# project.net
KiCad netlist of a schematic drawn in EAGLE
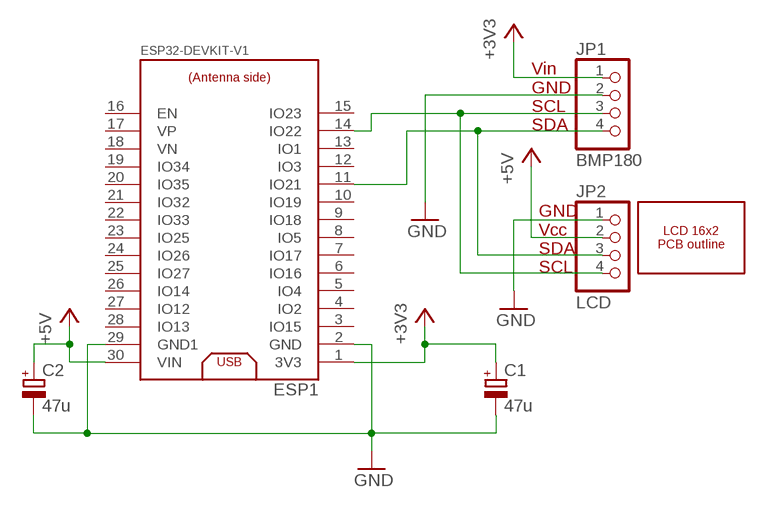
[diagram p0: schematic, sheet 1]

(export (version "E")
  (design (tool "Eeschema 10.0.6"))
  (components
    (comp (ref "C1")
      (value "47u")
      (footprint "eagle-import:E2,5-6E")
      (libsource (lib "eagle-import") (part "CPOL-EUE2,5-6E"))
    )
    (comp (ref "C2")
      (value "47u")
      (footprint "eagle-import:E2,5-6E")
      (libsource (lib "eagle-import") (part "CPOL-EUE2,5-6E"))
    )
    (comp (ref "ESP1")
      (value "ESP32DEVKITV1")
      (footprint "eagle-import:ESP32-DEVKITV1")
      (libsource (lib "eagle-import") (part "ESP32DEVKITV1"))
    )
    (comp (ref "JP1")
      (value "BMP180")
      (footprint "eagle-import:1X04")
      (libsource (lib "eagle-import") (part "PINHD-1X4"))
    )
    (comp (ref "JP2")
      (value "LCD")
      (footprint "eagle-import:1X04")
      (libsource (lib "eagle-import") (part "PINHD-1X4"))
    )
    (comp (ref "LCD1")
      (value "OUTLINES")
      (footprint "eagle-import:LCD162-OUTLINE")
      (libsource (lib "eagle-import") (part "OUTLINES"))
    )
  )
  (nets
    (net (code "1") (name "+3V3") (class "Default")
      (node (ref "C1") (pin "+") (pinfunction "+_+") (pintype "passive"))
      (node (ref "ESP1") (pin "1") (pinfunction "3V3_1") (pintype "bidirectional"))
      (node (ref "JP1") (pin "1") (pinfunction "1_1") (pintype "passive"))
    )
    (net (code "2") (name "+5V") (class "Default")
      (node (ref "C2") (pin "+") (pinfunction "+_+") (pintype "passive"))
      (node (ref "ESP1") (pin "30") (pinfunction "VIN_30") (pintype "bidirectional"))
      (node (ref "JP2") (pin "2") (pinfunction "2_2") (pintype "passive"))
    )
    (net (code "3") (name "GND") (class "Default")
      (node (ref "C1") (pin "-") (pinfunction "-_-") (pintype "passive"))
      (node (ref "C2") (pin "-") (pinfunction "-_-") (pintype "passive"))
      (node (ref "ESP1") (pin "2") (pinfunction "GND_2") (pintype "bidirectional"))
      (node (ref "ESP1") (pin "29") (pinfunction "GND1_29") (pintype "bidirectional"))
      (node (ref "JP1") (pin "2") (pinfunction "2_2") (pintype "passive"))
      (node (ref "JP2") (pin "1") (pinfunction "1_1") (pintype "passive"))
    )
    (net (code "4") (name "Net-(ESP1-IO21)") (class "Default")
      (node (ref "ESP1") (pin "11") (pinfunction "IO21_11") (pintype "bidirectional"))
      (node (ref "JP1") (pin "4") (pinfunction "4_4") (pintype "passive"))
      (node (ref "JP2") (pin "3") (pinfunction "3_3") (pintype "passive"))
    )
    (net (code "5") (name "Net-(ESP1-IO22)") (class "Default")
      (node (ref "ESP1") (pin "14") (pinfunction "IO22_14") (pintype "bidirectional"))
      (node (ref "JP1") (pin "3") (pinfunction "3_3") (pintype "passive"))
      (node (ref "JP2") (pin "4") (pinfunction "4_4") (pintype "passive"))
    )
    (net (code "6") (name "unconnected-(ESP1-EN-Pad16)") (class "Default")
      (node (ref "ESP1") (pin "16") (pinfunction "EN_16") (pintype "bidirectional"))
    )
    (net (code "7") (name "unconnected-(ESP1-IO1-Pad13)") (class "Default")
      (node (ref "ESP1") (pin "13") (pinfunction "IO1_13") (pintype "bidirectional"))
    )
    (net (code "8") (name "unconnected-(ESP1-IO2-Pad4)") (class "Default")
      (node (ref "ESP1") (pin "4") (pinfunction "IO2_4") (pintype "bidirectional"))
    )
    (net (code "9") (name "unconnected-(ESP1-IO3-Pad12)") (class "Default")
      (node (ref "ESP1") (pin "12") (pinfunction "IO3_12") (pintype "bidirectional"))
    )
    (net (code "10") (name "unconnected-(ESP1-IO4-Pad5)") (class "Default")
      (node (ref "ESP1") (pin "5") (pinfunction "IO4_5") (pintype "bidirectional"))
    )
    (net (code "11") (name "unconnected-(ESP1-IO5-Pad8)") (class "Default")
      (node (ref "ESP1") (pin "8") (pinfunction "IO5_8") (pintype "bidirectional"))
    )
    (net (code "12") (name "unconnected-(ESP1-IO12-Pad27)") (class "Default")
      (node (ref "ESP1") (pin "27") (pinfunction "IO12_27") (pintype "bidirectional"))
    )
    (net (code "13") (name "unconnected-(ESP1-IO13-Pad28)") (class "Default")
      (node (ref "ESP1") (pin "28") (pinfunction "IO13_28") (pintype "bidirectional"))
    )
    (net (code "14") (name "unconnected-(ESP1-IO14-Pad26)") (class "Default")
      (node (ref "ESP1") (pin "26") (pinfunction "IO14_26") (pintype "bidirectional"))
    )
    (net (code "15") (name "unconnected-(ESP1-IO15-Pad3)") (class "Default")
      (node (ref "ESP1") (pin "3") (pinfunction "IO15_3") (pintype "bidirectional"))
    )
    (net (code "16") (name "unconnected-(ESP1-IO16-Pad6)") (class "Default")
      (node (ref "ESP1") (pin "6") (pinfunction "IO16_6") (pintype "bidirectional"))
    )
    (net (code "17") (name "unconnected-(ESP1-IO17-Pad7)") (class "Default")
      (node (ref "ESP1") (pin "7") (pinfunction "IO17_7") (pintype "bidirectional"))
    )
    (net (code "18") (name "unconnected-(ESP1-IO18-Pad9)") (class "Default")
      (node (ref "ESP1") (pin "9") (pinfunction "IO18_9") (pintype "bidirectional"))
    )
    (net (code "19") (name "unconnected-(ESP1-IO19-Pad10)") (class "Default")
      (node (ref "ESP1") (pin "10") (pinfunction "IO19_10") (pintype "bidirectional"))
    )
    (net (code "20") (name "unconnected-(ESP1-IO23-Pad15)") (class "Default")
      (node (ref "ESP1") (pin "15") (pinfunction "IO23_15") (pintype "bidirectional"))
    )
    (net (code "21") (name "unconnected-(ESP1-IO25-Pad23)") (class "Default")
      (node (ref "ESP1") (pin "23") (pinfunction "IO25_23") (pintype "bidirectional"))
    )
    (net (code "22") (name "unconnected-(ESP1-IO26-Pad24)") (class "Default")
      (node (ref "ESP1") (pin "24") (pinfunction "IO26_24") (pintype "bidirectional"))
    )
    (net (code "23") (name "unconnected-(ESP1-IO27-Pad25)") (class "Default")
      (node (ref "ESP1") (pin "25") (pinfunction "IO27_25") (pintype "bidirectional"))
    )
    (net (code "24") (name "unconnected-(ESP1-IO32-Pad21)") (class "Default")
      (node (ref "ESP1") (pin "21") (pinfunction "IO32_21") (pintype "bidirectional"))
    )
    (net (code "25") (name "unconnected-(ESP1-IO33-Pad22)") (class "Default")
      (node (ref "ESP1") (pin "22") (pinfunction "IO33_22") (pintype "bidirectional"))
    )
    (net (code "26") (name "unconnected-(ESP1-IO34-Pad19)") (class "Default")
      (node (ref "ESP1") (pin "19") (pinfunction "IO34_19") (pintype "bidirectional"))
    )
    (net (code "27") (name "unconnected-(ESP1-IO35-Pad20)") (class "Default")
      (node (ref "ESP1") (pin "20") (pinfunction "IO35_20") (pintype "bidirectional"))
    )
    (net (code "28") (name "unconnected-(ESP1-VN-Pad18)") (class "Default")
      (node (ref "ESP1") (pin "18") (pinfunction "VN_18") (pintype "bidirectional"))
    )
    (net (code "29") (name "unconnected-(ESP1-VP-Pad17)") (class "Default")
      (node (ref "ESP1") (pin "17") (pinfunction "VP_17") (pintype "bidirectional"))
    )
  )
)
